# Cell_stretcher.net
KiCad netlist of a schematic drawn in EAGLE
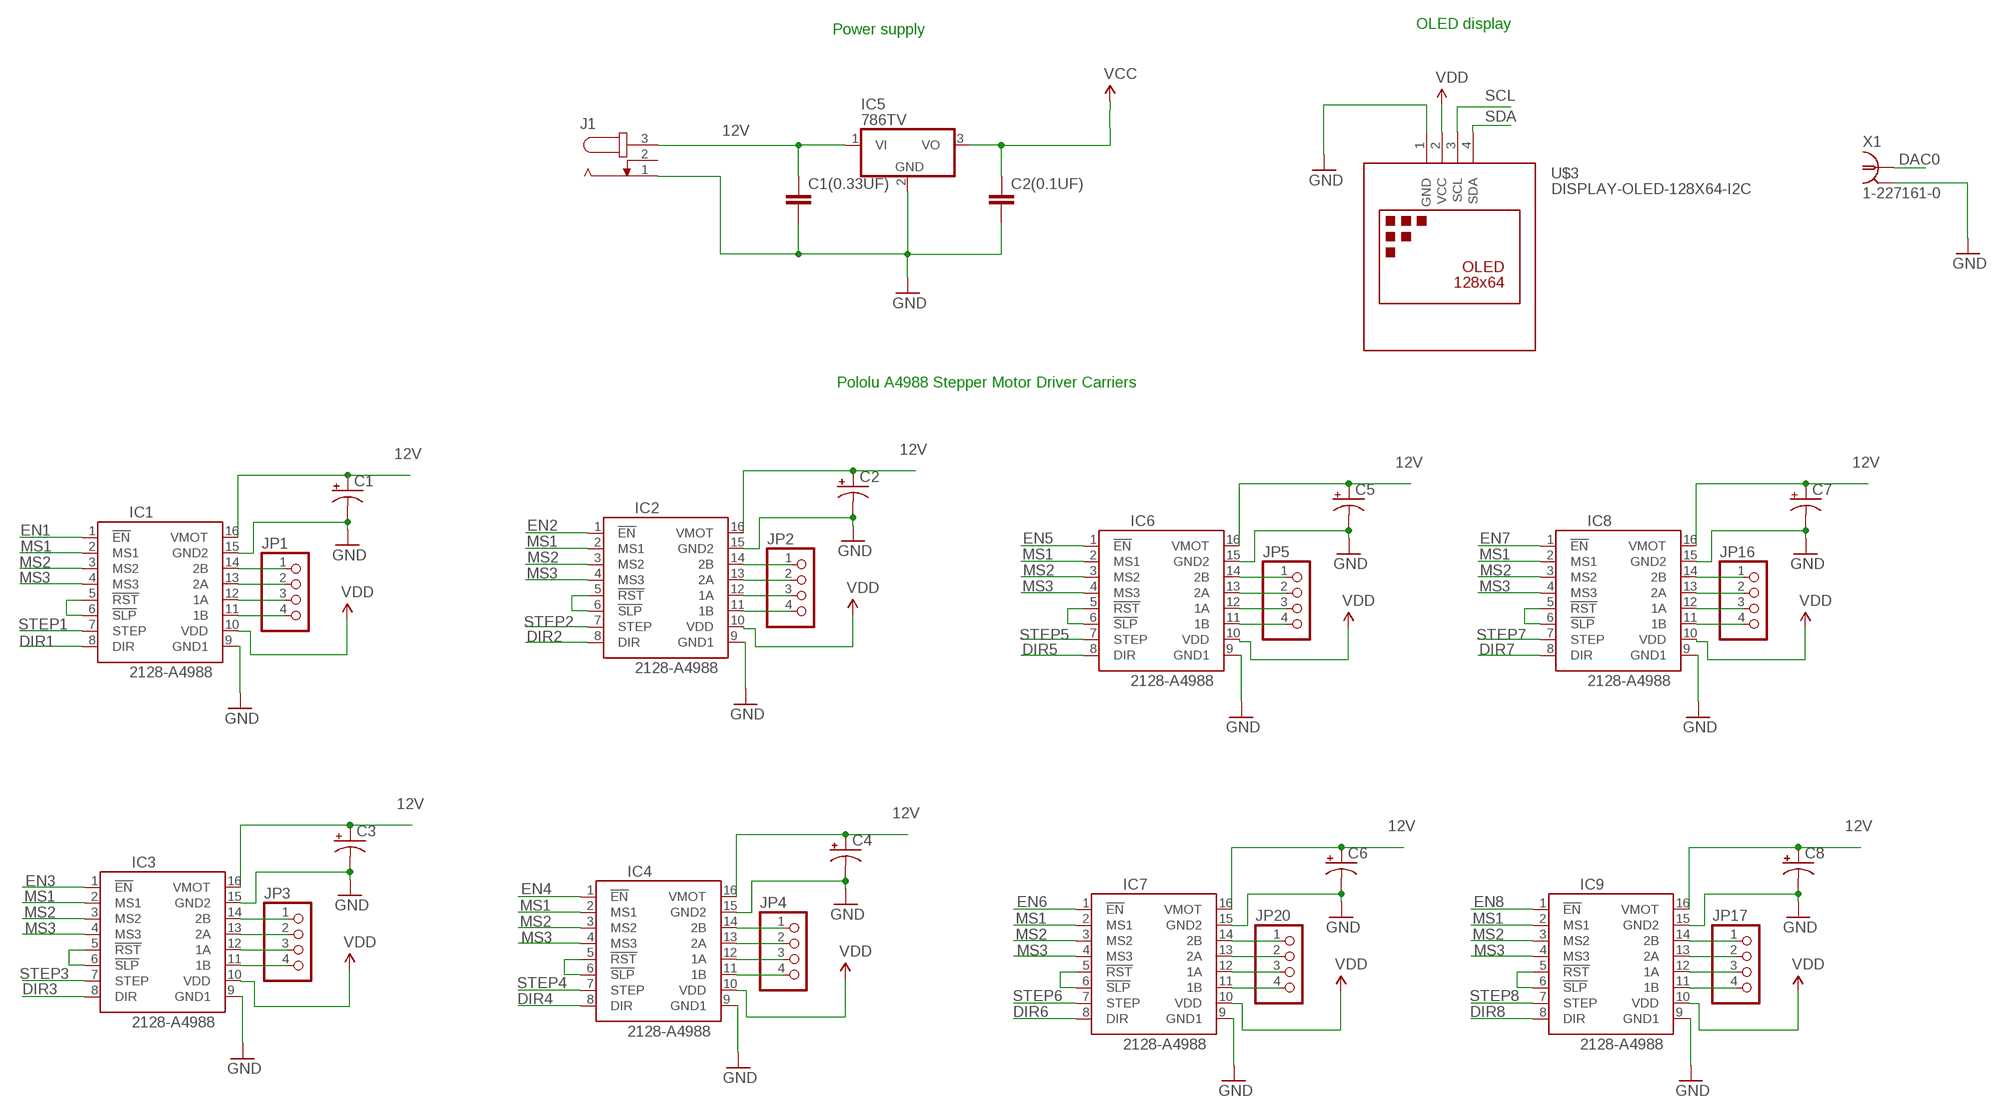
[diagram p0: schematic, sheet 1, part 1 of 2]
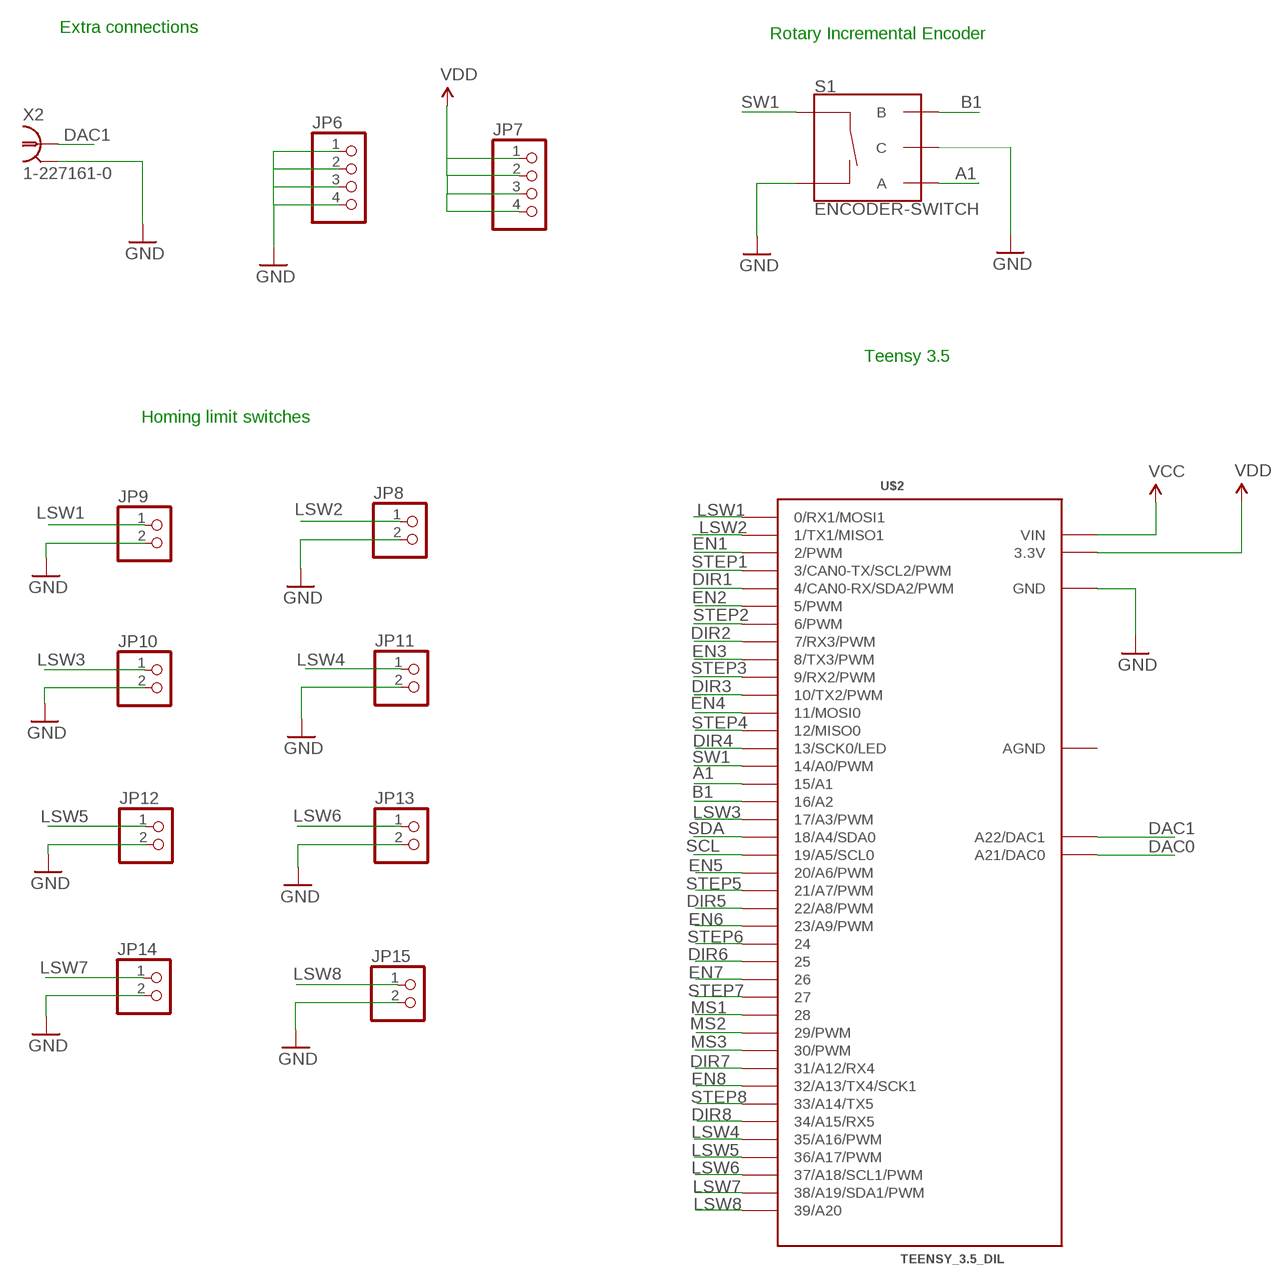
[diagram p1: schematic, sheet 1, part 2 of 2]

(export (version "E")
  (design (tool "Eeschema 10.0.6"))
  (components
    (comp (ref "C1")
      (value "CPOL-USE5-5")
      (footprint "eagle-import:E5-5")
      (libsource (lib "eagle-import") (part "CPOL-USE5-5"))
    )
    (comp (ref "C1(0.33UF)")
      (value "C2.5/4")
      (footprint "eagle-import:C2.5-4")
      (libsource (lib "eagle-import") (part "C2.5/4"))
    )
    (comp (ref "C2")
      (value "CPOL-USE5-5")
      (footprint "eagle-import:E5-5")
      (libsource (lib "eagle-import") (part "CPOL-USE5-5"))
    )
    (comp (ref "C2(0.1UF)")
      (value "C2.5/2")
      (footprint "eagle-import:C2.5-2")
      (libsource (lib "eagle-import") (part "C2.5/2"))
    )
    (comp (ref "C3")
      (value "CPOL-USE5-5")
      (footprint "eagle-import:E5-5")
      (libsource (lib "eagle-import") (part "CPOL-USE5-5"))
    )
    (comp (ref "C4")
      (value "CPOL-USE5-5")
      (footprint "eagle-import:E5-5")
      (libsource (lib "eagle-import") (part "CPOL-USE5-5"))
    )
    (comp (ref "C5")
      (value "CPOL-USE5-5")
      (footprint "eagle-import:E5-5")
      (libsource (lib "eagle-import") (part "CPOL-USE5-5"))
    )
    (comp (ref "C6")
      (value "CPOL-USE5-5")
      (footprint "eagle-import:E5-5")
      (libsource (lib "eagle-import") (part "CPOL-USE5-5"))
    )
    (comp (ref "C7")
      (value "CPOL-USE5-5")
      (footprint "eagle-import:E5-5")
      (libsource (lib "eagle-import") (part "CPOL-USE5-5"))
    )
    (comp (ref "C8")
      (value "CPOL-USE5-5")
      (footprint "eagle-import:E5-5")
      (libsource (lib "eagle-import") (part "CPOL-USE5-5"))
    )
    (comp (ref "IC1")
      (value "2128-A4988")
      (footprint "eagle-import:A4988")
      (libsource (lib "eagle-import") (part "2128-A4988"))
    )
    (comp (ref "IC2")
      (value "2128-A4988")
      (footprint "eagle-import:A4988")
      (libsource (lib "eagle-import") (part "2128-A4988"))
    )
    (comp (ref "IC3")
      (value "2128-A4988")
      (footprint "eagle-import:A4988")
      (libsource (lib "eagle-import") (part "2128-A4988"))
    )
    (comp (ref "IC4")
      (value "2128-A4988")
      (footprint "eagle-import:A4988")
      (libsource (lib "eagle-import") (part "2128-A4988"))
    )
    (comp (ref "IC5")
      (value "786TV")
      (footprint "eagle-import:TO220V")
      (libsource (lib "eagle-import") (part "78TV6"))
    )
    (comp (ref "IC6")
      (value "2128-A4988")
      (footprint "eagle-import:A4988")
      (libsource (lib "eagle-import") (part "2128-A4988"))
    )
    (comp (ref "IC7")
      (value "2128-A4988")
      (footprint "eagle-import:A4988")
      (libsource (lib "eagle-import") (part "2128-A4988"))
    )
    (comp (ref "IC8")
      (value "2128-A4988")
      (footprint "eagle-import:A4988")
      (libsource (lib "eagle-import") (part "2128-A4988"))
    )
    (comp (ref "IC9")
      (value "2128-A4988")
      (footprint "eagle-import:A4988")
      (libsource (lib "eagle-import") (part "2128-A4988"))
    )
    (comp (ref "J1")
      (value "JACK-PLUG0")
      (footprint "eagle-import:SPC4077")
      (libsource (lib "eagle-import") (part "JACK-PLUG0"))
    )
    (comp (ref "JP1")
      (value "PINHD-1X4")
      (footprint "eagle-import:1X04")
      (libsource (lib "eagle-import") (part "PINHD-1X4"))
    )
    (comp (ref "JP2")
      (value "PINHD-1X4")
      (footprint "eagle-import:1X04")
      (libsource (lib "eagle-import") (part "PINHD-1X4"))
    )
    (comp (ref "JP3")
      (value "PINHD-1X4")
      (footprint "eagle-import:1X04")
      (libsource (lib "eagle-import") (part "PINHD-1X4"))
    )
    (comp (ref "JP4")
      (value "PINHD-1X4")
      (footprint "eagle-import:1X04")
      (libsource (lib "eagle-import") (part "PINHD-1X4"))
    )
    (comp (ref "JP5")
      (value "PINHD-1X4")
      (footprint "eagle-import:1X04")
      (libsource (lib "eagle-import") (part "PINHD-1X4"))
    )
    (comp (ref "JP6")
      (value "PINHD-1X4")
      (footprint "eagle-import:1X04")
      (libsource (lib "eagle-import") (part "PINHD-1X4"))
    )
    (comp (ref "JP7")
      (value "PINHD-1X4")
      (footprint "eagle-import:1X04")
      (libsource (lib "eagle-import") (part "PINHD-1X4"))
    )
    (comp (ref "JP8")
      (value "PINHD-1X2")
      (footprint "eagle-import:1X02")
      (libsource (lib "eagle-import") (part "PINHD-1X2"))
    )
    (comp (ref "JP9")
      (value "PINHD-1X2")
      (footprint "eagle-import:1X02")
      (libsource (lib "eagle-import") (part "PINHD-1X2"))
    )
    (comp (ref "JP10")
      (value "PINHD-1X2")
      (footprint "eagle-import:1X02")
      (libsource (lib "eagle-import") (part "PINHD-1X2"))
    )
    (comp (ref "JP11")
      (value "PINHD-1X2")
      (footprint "eagle-import:1X02")
      (libsource (lib "eagle-import") (part "PINHD-1X2"))
    )
    (comp (ref "JP12")
      (value "PINHD-1X2")
      (footprint "eagle-import:1X02")
      (libsource (lib "eagle-import") (part "PINHD-1X2"))
    )
    (comp (ref "JP13")
      (value "PINHD-1X2")
      (footprint "eagle-import:1X02")
      (libsource (lib "eagle-import") (part "PINHD-1X2"))
    )
    (comp (ref "JP14")
      (value "PINHD-1X2")
      (footprint "eagle-import:1X02")
      (libsource (lib "eagle-import") (part "PINHD-1X2"))
    )
    (comp (ref "JP15")
      (value "PINHD-1X2")
      (footprint "eagle-import:1X02")
      (libsource (lib "eagle-import") (part "PINHD-1X2"))
    )
    (comp (ref "JP16")
      (value "PINHD-1X4")
      (footprint "eagle-import:1X04")
      (libsource (lib "eagle-import") (part "PINHD-1X4"))
    )
    (comp (ref "JP17")
      (value "PINHD-1X4")
      (footprint "eagle-import:1X04")
      (libsource (lib "eagle-import") (part "PINHD-1X4"))
    )
    (comp (ref "JP20")
      (value "PINHD-1X4")
      (footprint "eagle-import:1X04")
      (libsource (lib "eagle-import") (part "PINHD-1X4"))
    )
    (comp (ref "S1")
      (value "ENCODER-SWITCH")
      (footprint "eagle-import:ROTARY_ENC_PLAIN")
      (libsource (lib "eagle-import") (part "ENCODER-SWITCH"))
    )
    (comp (ref "U$2")
      (value "TEENSY_3.5_DIL")
      (footprint "eagle-import:TEENSY_3.5_DIL")
      (libsource (lib "eagle-import") (part "TEENSY_3.5_DIL"))
    )
    (comp (ref "U$3")
      (value "DISPLAY-OLED-128X64-I2C")
      (footprint "eagle-import:DISPLAY-OLED-128X64-I2C")
      (libsource (lib "eagle-import") (part "DISPLAY-OLED-128X64-I2C"))
    )
    (comp (ref "X1")
      (value "1-227161-0")
      (footprint "eagle-import:AMP_227161")
      (fields (field (name "MF") "TYCO ELECTRONICS") (field (name "MPN") "1-227161"))
      (libsource (lib "eagle-import") (part "?2271611--0"))
    )
    (comp (ref "X2")
      (value "1-227161-0")
      (footprint "eagle-import:AMP_227161")
      (fields (field (name "MF") "TYCO ELECTRONICS") (field (name "MPN") "1-227161"))
      (libsource (lib "eagle-import") (part "?2271611--0"))
    )
  )
  (nets
    (net (code "1") (name "/12V") (class "Default")
      (node (ref "C1") (pin "+") (pinfunction "+_+") (pintype "passive"))
      (node (ref "C1(0.33UF)") (pin "1") (pinfunction "1_1") (pintype "passive"))
      (node (ref "C2") (pin "+") (pinfunction "+_+") (pintype "passive"))
      (node (ref "C3") (pin "+") (pinfunction "+_+") (pintype "passive"))
      (node (ref "C4") (pin "+") (pinfunction "+_+") (pintype "passive"))
      (node (ref "C5") (pin "+") (pinfunction "+_+") (pintype "passive"))
      (node (ref "C6") (pin "+") (pinfunction "+_+") (pintype "passive"))
      (node (ref "C7") (pin "+") (pinfunction "+_+") (pintype "passive"))
      (node (ref "C8") (pin "+") (pinfunction "+_+") (pintype "passive"))
      (node (ref "IC1") (pin "16") (pinfunction "VMOT_16") (pintype "power_in"))
      (node (ref "IC2") (pin "16") (pinfunction "VMOT_16") (pintype "power_in"))
      (node (ref "IC3") (pin "16") (pinfunction "VMOT_16") (pintype "power_in"))
      (node (ref "IC4") (pin "16") (pinfunction "VMOT_16") (pintype "power_in"))
      (node (ref "IC5") (pin "1") (pinfunction "VI_1") (pintype "input"))
      (node (ref "IC6") (pin "16") (pinfunction "VMOT_16") (pintype "power_in"))
      (node (ref "IC7") (pin "16") (pinfunction "VMOT_16") (pintype "power_in"))
      (node (ref "IC8") (pin "16") (pinfunction "VMOT_16") (pintype "power_in"))
      (node (ref "IC9") (pin "16") (pinfunction "VMOT_16") (pintype "power_in"))
      (node (ref "J1") (pin "3") (pinfunction "3_3") (pintype "passive"))
    )
    (net (code "2") (name "/A1") (class "Default")
      (node (ref "S1") (pin "A") (pinfunction "A_A") (pintype "bidirectional"))
      (node (ref "U$2") (pin "15/A1") (pinfunction "15/A1_15/A1") (pintype "bidirectional"))
    )
    (net (code "3") (name "/AGND") (class "Default")
      (node (ref "U$2") (pin "AGND") (pinfunction "AGND_AGND") (pintype "power_in"))
    )
    (net (code "4") (name "/B1") (class "Default")
      (node (ref "S1") (pin "B") (pinfunction "B_B") (pintype "bidirectional"))
      (node (ref "U$2") (pin "16/A2") (pinfunction "16/A2_16/A2") (pintype "bidirectional"))
    )
    (net (code "5") (name "/DAC0") (class "Default")
      (node (ref "U$2") (pin "A21") (pinfunction "A21/DAC0_A21") (pintype "bidirectional"))
      (node (ref "X1") (pin "1") (pinfunction "1_1") (pintype "passive"))
    )
    (net (code "6") (name "/DAC1") (class "Default")
      (node (ref "U$2") (pin "A22") (pinfunction "A22/DAC1_A22") (pintype "bidirectional"))
      (node (ref "X2") (pin "1") (pinfunction "1_1") (pintype "passive"))
    )
    (net (code "7") (name "/DIR1") (class "Default")
      (node (ref "IC1") (pin "8") (pinfunction "DIR_8") (pintype "input"))
      (node (ref "U$2") (pin "4") (pinfunction "4/CAN0-RX/SDA2/PWM_4") (pintype "bidirectional"))
    )
    (net (code "8") (name "/DIR2") (class "Default")
      (node (ref "IC2") (pin "8") (pinfunction "DIR_8") (pintype "input"))
      (node (ref "U$2") (pin "7") (pinfunction "7/RX3/PWM_7") (pintype "bidirectional"))
    )
    (net (code "9") (name "/DIR3") (class "Default")
      (node (ref "IC3") (pin "8") (pinfunction "DIR_8") (pintype "input"))
      (node (ref "U$2") (pin "10") (pinfunction "10/TX2/PWM_10") (pintype "bidirectional"))
    )
    (net (code "10") (name "/DIR4") (class "Default")
      (node (ref "IC4") (pin "8") (pinfunction "DIR_8") (pintype "input"))
      (node (ref "U$2") (pin "13") (pinfunction "13/SCK0/LED_13") (pintype "bidirectional"))
    )
    (net (code "11") (name "/DIR5") (class "Default")
      (node (ref "IC6") (pin "8") (pinfunction "DIR_8") (pintype "input"))
      (node (ref "U$2") (pin "22/A8") (pinfunction "22/A8/PWM_22/A8") (pintype "bidirectional"))
    )
    (net (code "12") (name "/DIR6") (class "Default")
      (node (ref "IC7") (pin "8") (pinfunction "DIR_8") (pintype "input"))
      (node (ref "U$2") (pin "25") (pinfunction "25_25") (pintype "bidirectional"))
    )
    (net (code "13") (name "/DIR7") (class "Default")
      (node (ref "IC8") (pin "8") (pinfunction "DIR_8") (pintype "input"))
      (node (ref "U$2") (pin "31/A12") (pinfunction "31/A12/RX4_31/A12") (pintype "bidirectional"))
    )
    (net (code "14") (name "/DIR8") (class "Default")
      (node (ref "IC9") (pin "8") (pinfunction "DIR_8") (pintype "input"))
      (node (ref "U$2") (pin "34/A15") (pinfunction "34/A15/RX5_34/A15") (pintype "bidirectional"))
    )
    (net (code "15") (name "/EN1") (class "Default")
      (node (ref "IC1") (pin "1") (pinfunction "~{EN}_1") (pintype "passive"))
      (node (ref "U$2") (pin "2") (pinfunction "2/PWM_2") (pintype "bidirectional"))
    )
    (net (code "16") (name "/EN2") (class "Default")
      (node (ref "IC2") (pin "1") (pinfunction "~{EN}_1") (pintype "passive"))
      (node (ref "U$2") (pin "5") (pinfunction "5/PWM_5") (pintype "bidirectional"))
    )
    (net (code "17") (name "/EN3") (class "Default")
      (node (ref "IC3") (pin "1") (pinfunction "~{EN}_1") (pintype "passive"))
      (node (ref "U$2") (pin "8") (pinfunction "8/TX3/PWM_8") (pintype "bidirectional"))
    )
    (net (code "18") (name "/EN4") (class "Default")
      (node (ref "IC4") (pin "1") (pinfunction "~{EN}_1") (pintype "passive"))
      (node (ref "U$2") (pin "11") (pinfunction "11/MOSI0_11") (pintype "bidirectional"))
    )
    (net (code "19") (name "/EN5") (class "Default")
      (node (ref "IC6") (pin "1") (pinfunction "~{EN}_1") (pintype "passive"))
      (node (ref "U$2") (pin "20/A6") (pinfunction "20/A6/PWM_20/A6") (pintype "bidirectional"))
    )
    (net (code "20") (name "/EN6") (class "Default")
      (node (ref "IC7") (pin "1") (pinfunction "~{EN}_1") (pintype "passive"))
      (node (ref "U$2") (pin "23/A9") (pinfunction "23/A9/PWM_23/A9") (pintype "bidirectional"))
    )
    (net (code "21") (name "/EN7") (class "Default")
      (node (ref "IC8") (pin "1") (pinfunction "~{EN}_1") (pintype "passive"))
      (node (ref "U$2") (pin "26") (pinfunction "26_26") (pintype "bidirectional"))
    )
    (net (code "22") (name "/EN8") (class "Default")
      (node (ref "IC9") (pin "1") (pinfunction "~{EN}_1") (pintype "passive"))
      (node (ref "U$2") (pin "32/A13") (pinfunction "32/A13/TX4/SCK1_32/A13") (pintype "bidirectional"))
    )
    (net (code "23") (name "/LSW1") (class "Default")
      (node (ref "JP9") (pin "1") (pinfunction "1_1") (pintype "passive"))
      (node (ref "U$2") (pin "0") (pinfunction "0/RX1/MOSI1_0") (pintype "bidirectional"))
    )
    (net (code "24") (name "/LSW2") (class "Default")
      (node (ref "JP8") (pin "1") (pinfunction "1_1") (pintype "passive"))
      (node (ref "U$2") (pin "1") (pinfunction "1/TX1/MISO1_1") (pintype "bidirectional"))
    )
    (net (code "25") (name "/LSW3") (class "Default")
      (node (ref "JP10") (pin "1") (pinfunction "1_1") (pintype "passive"))
      (node (ref "U$2") (pin "17/A3") (pinfunction "17/A3/PWM_17/A3") (pintype "bidirectional"))
    )
    (net (code "26") (name "/LSW4") (class "Default")
      (node (ref "JP11") (pin "1") (pinfunction "1_1") (pintype "passive"))
      (node (ref "U$2") (pin "35/A16") (pinfunction "35/A16/PWM_35/A16") (pintype "bidirectional"))
    )
    (net (code "27") (name "/LSW5") (class "Default")
      (node (ref "JP12") (pin "1") (pinfunction "1_1") (pintype "passive"))
      (node (ref "U$2") (pin "36/A17") (pinfunction "36/A17/PWM_36/A17") (pintype "bidirectional"))
    )
    (net (code "28") (name "/LSW6") (class "Default")
      (node (ref "JP13") (pin "1") (pinfunction "1_1") (pintype "passive"))
      (node (ref "U$2") (pin "37/A18") (pinfunction "37/A18/SCL1/PWM_37/A18") (pintype "bidirectional"))
    )
    (net (code "29") (name "/LSW7") (class "Default")
      (node (ref "JP14") (pin "1") (pinfunction "1_1") (pintype "passive"))
      (node (ref "U$2") (pin "38/A19") (pinfunction "38/A19/SDA1/PWM_38/A19") (pintype "bidirectional"))
    )
    (net (code "30") (name "/LSW8") (class "Default")
      (node (ref "JP15") (pin "1") (pinfunction "1_1") (pintype "passive"))
      (node (ref "U$2") (pin "39/A20") (pinfunction "39/A20_39/A20") (pintype "bidirectional"))
    )
    (net (code "31") (name "/MS1") (class "Default")
      (node (ref "IC1") (pin "2") (pinfunction "MS1_2") (pintype "passive"))
      (node (ref "IC2") (pin "2") (pinfunction "MS1_2") (pintype "passive"))
      (node (ref "IC3") (pin "2") (pinfunction "MS1_2") (pintype "passive"))
      (node (ref "IC4") (pin "2") (pinfunction "MS1_2") (pintype "passive"))
      (node (ref "IC6") (pin "2") (pinfunction "MS1_2") (pintype "passive"))
      (node (ref "IC7") (pin "2") (pinfunction "MS1_2") (pintype "passive"))
      (node (ref "IC8") (pin "2") (pinfunction "MS1_2") (pintype "passive"))
      (node (ref "IC9") (pin "2") (pinfunction "MS1_2") (pintype "passive"))
      (node (ref "U$2") (pin "28") (pinfunction "28_28") (pintype "bidirectional"))
    )
    (net (code "32") (name "/MS2") (class "Default")
      (node (ref "IC1") (pin "3") (pinfunction "MS2_3") (pintype "passive"))
      (node (ref "IC2") (pin "3") (pinfunction "MS2_3") (pintype "passive"))
      (node (ref "IC3") (pin "3") (pinfunction "MS2_3") (pintype "passive"))
      (node (ref "IC4") (pin "3") (pinfunction "MS2_3") (pintype "passive"))
      (node (ref "IC6") (pin "3") (pinfunction "MS2_3") (pintype "passive"))
      (node (ref "IC7") (pin "3") (pinfunction "MS2_3") (pintype "passive"))
      (node (ref "IC8") (pin "3") (pinfunction "MS2_3") (pintype "passive"))
      (node (ref "IC9") (pin "3") (pinfunction "MS2_3") (pintype "passive"))
      (node (ref "U$2") (pin "29") (pinfunction "29/PWM_29") (pintype "bidirectional"))
    )
    (net (code "33") (name "/MS3") (class "Default")
      (node (ref "IC1") (pin "4") (pinfunction "MS3_4") (pintype "passive"))
      (node (ref "IC2") (pin "4") (pinfunction "MS3_4") (pintype "passive"))
      (node (ref "IC3") (pin "4") (pinfunction "MS3_4") (pintype "passive"))
      (node (ref "IC4") (pin "4") (pinfunction "MS3_4") (pintype "passive"))
      (node (ref "IC6") (pin "4") (pinfunction "MS3_4") (pintype "passive"))
      (node (ref "IC7") (pin "4") (pinfunction "MS3_4") (pintype "passive"))
      (node (ref "IC8") (pin "4") (pinfunction "MS3_4") (pintype "passive"))
      (node (ref "IC9") (pin "4") (pinfunction "MS3_4") (pintype "passive"))
      (node (ref "U$2") (pin "30") (pinfunction "30/PWM_30") (pintype "bidirectional"))
    )
    (net (code "34") (name "/SCL") (class "Default")
      (node (ref "U$2") (pin "19/A5") (pinfunction "19/A5/SCL0_19/A5") (pintype "bidirectional"))
      (node (ref "U$3") (pin "3") (pinfunction "SCL_3") (pintype "bidirectional"))
    )
    (net (code "35") (name "/SDA") (class "Default")
      (node (ref "U$2") (pin "18/A4") (pinfunction "18/A4/SDA0_18/A4") (pintype "bidirectional"))
      (node (ref "U$3") (pin "4") (pinfunction "SDA_4") (pintype "bidirectional"))
    )
    (net (code "36") (name "/STEP1") (class "Default")
      (node (ref "IC1") (pin "7") (pinfunction "STEP_7") (pintype "input"))
      (node (ref "U$2") (pin "3") (pinfunction "3/CAN0-TX/SCL2/PWM_3") (pintype "bidirectional"))
    )
    (net (code "37") (name "/STEP2") (class "Default")
      (node (ref "IC2") (pin "7") (pinfunction "STEP_7") (pintype "input"))
      (node (ref "U$2") (pin "6") (pinfunction "6/PWM_6") (pintype "bidirectional"))
    )
    (net (code "38") (name "/STEP3") (class "Default")
      (node (ref "IC3") (pin "7") (pinfunction "STEP_7") (pintype "input"))
      (node (ref "U$2") (pin "9") (pinfunction "9/RX2/PWM_9") (pintype "bidirectional"))
    )
    (net (code "39") (name "/STEP4") (class "Default")
      (node (ref "IC4") (pin "7") (pinfunction "STEP_7") (pintype "input"))
      (node (ref "U$2") (pin "12") (pinfunction "12/MISO0_12") (pintype "bidirectional"))
    )
    (net (code "40") (name "/STEP5") (class "Default")
      (node (ref "IC6") (pin "7") (pinfunction "STEP_7") (pintype "input"))
      (node (ref "U$2") (pin "21/A7") (pinfunction "21/A7/PWM_21/A7") (pintype "bidirectional"))
    )
    (net (code "41") (name "/STEP6") (class "Default")
      (node (ref "IC7") (pin "7") (pinfunction "STEP_7") (pintype "input"))
      (node (ref "U$2") (pin "24") (pinfunction "24_24") (pintype "bidirectional"))
    )
    (net (code "42") (name "/STEP7") (class "Default")
      (node (ref "IC8") (pin "7") (pinfunction "STEP_7") (pintype "input"))
      (node (ref "U$2") (pin "27") (pinfunction "27_27") (pintype "bidirectional"))
    )
    (net (code "43") (name "/STEP8") (class "Default")
      (node (ref "IC9") (pin "7") (pinfunction "STEP_7") (pintype "input"))
      (node (ref "U$2") (pin "33/A14") (pinfunction "33/A14/TX5_33/A14") (pintype "bidirectional"))
    )
    (net (code "44") (name "/SW1") (class "Default")
      (node (ref "S1") (pin "SW+") (pinfunction "SW+_SW+") (pintype "bidirectional"))
      (node (ref "U$2") (pin "14/A0") (pinfunction "14/A0/PWM_14/A0") (pintype "bidirectional"))
    )
    (net (code "45") (name "GND") (class "Default")
      (node (ref "C1") (pin "-") (pinfunction "-_-") (pintype "passive"))
      (node (ref "C1(0.33UF)") (pin "2") (pinfunction "2_2") (pintype "passive"))
      (node (ref "C2") (pin "-") (pinfunction "-_-") (pintype "passive"))
      (node (ref "C2(0.1UF)") (pin "2") (pinfunction "2_2") (pintype "passive"))
      (node (ref "C3") (pin "-") (pinfunction "-_-") (pintype "passive"))
      (node (ref "C4") (pin "-") (pinfunction "-_-") (pintype "passive"))
      (node (ref "C5") (pin "-") (pinfunction "-_-") (pintype "passive"))
      (node (ref "C6") (pin "-") (pinfunction "-_-") (pintype "passive"))
      (node (ref "C7") (pin "-") (pinfunction "-_-") (pintype "passive"))
      (node (ref "C8") (pin "-") (pinfunction "-_-") (pintype "passive"))
      (node (ref "IC1") (pin "15") (pinfunction "GND2_15") (pintype "power_in"))
      (node (ref "IC1") (pin "9") (pinfunction "GND1_9") (pintype "power_in"))
      (node (ref "IC2") (pin "15") (pinfunction "GND2_15") (pintype "power_in"))
      (node (ref "IC2") (pin "9") (pinfunction "GND1_9") (pintype "power_in"))
      (node (ref "IC3") (pin "15") (pinfunction "GND2_15") (pintype "power_in"))
      (node (ref "IC3") (pin "9") (pinfunction "GND1_9") (pintype "power_in"))
      (node (ref "IC4") (pin "15") (pinfunction "GND2_15") (pintype "power_in"))
      (node (ref "IC4") (pin "9") (pinfunction "GND1_9") (pintype "power_in"))
      (node (ref "IC5") (pin "2") (pinfunction "GND_2") (pintype "passive"))
      (node (ref "IC6") (pin "15") (pinfunction "GND2_15") (pintype "power_in"))
      (node (ref "IC6") (pin "9") (pinfunction "GND1_9") (pintype "power_in"))
      (node (ref "IC7") (pin "15") (pinfunction "GND2_15") (pintype "power_in"))
      (node (ref "IC7") (pin "9") (pinfunction "GND1_9") (pintype "power_in"))
      (node (ref "IC8") (pin "15") (pinfunction "GND2_15") (pintype "power_in"))
      (node (ref "IC8") (pin "9") (pinfunction "GND1_9") (pintype "power_in"))
      (node (ref "IC9") (pin "15") (pinfunction "GND2_15") (pintype "power_in"))
      (node (ref "IC9") (pin "9") (pinfunction "GND1_9") (pintype "power_in"))
      (node (ref "J1") (pin "1") (pinfunction "1_1") (pintype "passive"))
      (node (ref "JP10") (pin "2") (pinfunction "2_2") (pintype "passive"))
      (node (ref "JP11") (pin "2") (pinfunction "2_2") (pintype "passive"))
      (node (ref "JP12") (pin "2") (pinfunction "2_2") (pintype "passive"))
      (node (ref "JP13") (pin "2") (pinfunction "2_2") (pintype "passive"))
      (node (ref "JP14") (pin "2") (pinfunction "2_2") (pintype "passive"))
      (node (ref "JP15") (pin "2") (pinfunction "2_2") (pintype "passive"))
      (node (ref "JP6") (pin "1") (pinfunction "1_1") (pintype "passive"))
      (node (ref "JP6") (pin "2") (pinfunction "2_2") (pintype "passive"))
      (node (ref "JP6") (pin "3") (pinfunction "3_3") (pintype "passive"))
      (node (ref "JP6") (pin "4") (pinfunction "4_4") (pintype "passive"))
      (node (ref "JP8") (pin "2") (pinfunction "2_2") (pintype "passive"))
      (node (ref "JP9") (pin "2") (pinfunction "2_2") (pintype "passive"))
      (node (ref "S1") (pin "C") (pinfunction "C_C") (pintype "bidirectional"))
      (node (ref "S1") (pin "SW-") (pinfunction "SW-_SW-") (pintype "bidirectional"))
      (node (ref "U$2") (pin "GND") (pinfunction "GND_GND") (pintype "power_in"))
      (node (ref "U$2") (pin "GND1") (pinfunction "GND_GND1") (pintype "power_in"))
      (node (ref "U$3") (pin "1") (pinfunction "GND_1") (pintype "power_in"))
      (node (ref "X1") (pin "2") (pinfunction "2_2") (pintype "passive"))
      (node (ref "X2") (pin "2") (pinfunction "2_2") (pintype "passive"))
    )
    (net (code "46") (name "Net-(IC1-1A)") (class "Default")
      (node (ref "IC1") (pin "12") (pinfunction "1A_12") (pintype "output"))
      (node (ref "JP1") (pin "3") (pinfunction "3_3") (pintype "passive"))
    )
    (net (code "47") (name "Net-(IC1-1B)") (class "Default")
      (node (ref "IC1") (pin "11") (pinfunction "1B_11") (pintype "output"))
      (node (ref "JP1") (pin "4") (pinfunction "4_4") (pintype "passive"))
    )
    (net (code "48") (name "Net-(IC1-2A)") (class "Default")
      (node (ref "IC1") (pin "13") (pinfunction "2A_13") (pintype "output"))
      (node (ref "JP1") (pin "2") (pinfunction "2_2") (pintype "passive"))
    )
    (net (code "49") (name "Net-(IC1-2B)") (class "Default")
      (node (ref "IC1") (pin "14") (pinfunction "2B_14") (pintype "output"))
      (node (ref "JP1") (pin "1") (pinfunction "1_1") (pintype "passive"))
    )
    (net (code "50") (name "Net-(IC1-~{RST})") (class "Default")
      (node (ref "IC1") (pin "5") (pinfunction "~{RST}_5") (pintype "passive"))
      (node (ref "IC1") (pin "6") (pinfunction "~{SLP}_6") (pintype "passive"))
    )
    (net (code "51") (name "Net-(IC2-1A)") (class "Default")
      (node (ref "IC2") (pin "12") (pinfunction "1A_12") (pintype "output"))
      (node (ref "JP2") (pin "3") (pinfunction "3_3") (pintype "passive"))
    )
    (net (code "52") (name "Net-(IC2-1B)") (class "Default")
      (node (ref "IC2") (pin "11") (pinfunction "1B_11") (pintype "output"))
      (node (ref "JP2") (pin "4") (pinfunction "4_4") (pintype "passive"))
    )
    (net (code "53") (name "Net-(IC2-2A)") (class "Default")
      (node (ref "IC2") (pin "13") (pinfunction "2A_13") (pintype "output"))
      (node (ref "JP2") (pin "2") (pinfunction "2_2") (pintype "passive"))
    )
    (net (code "54") (name "Net-(IC2-2B)") (class "Default")
      (node (ref "IC2") (pin "14") (pinfunction "2B_14") (pintype "output"))
      (node (ref "JP2") (pin "1") (pinfunction "1_1") (pintype "passive"))
    )
    (net (code "55") (name "Net-(IC2-~{RST})") (class "Default")
      (node (ref "IC2") (pin "5") (pinfunction "~{RST}_5") (pintype "passive"))
      (node (ref "IC2") (pin "6") (pinfunction "~{SLP}_6") (pintype "passive"))
    )
    (net (code "56") (name "Net-(IC3-1A)") (class "Default")
      (node (ref "IC3") (pin "12") (pinfunction "1A_12") (pintype "output"))
      (node (ref "JP3") (pin "3") (pinfunction "3_3") (pintype "passive"))
    )
    (net (code "57") (name "Net-(IC3-1B)") (class "Default")
      (node (ref "IC3") (pin "11") (pinfunction "1B_11") (pintype "output"))
      (node (ref "JP3") (pin "4") (pinfunction "4_4") (pintype "passive"))
    )
    (net (code "58") (name "Net-(IC3-2A)") (class "Default")
      (node (ref "IC3") (pin "13") (pinfunction "2A_13") (pintype "output"))
      (node (ref "JP3") (pin "2") (pinfunction "2_2") (pintype "passive"))
    )
    (net (code "59") (name "Net-(IC3-2B)") (class "Default")
      (node (ref "IC3") (pin "14") (pinfunction "2B_14") (pintype "output"))
      (node (ref "JP3") (pin "1") (pinfunction "1_1") (pintype "passive"))
    )
    (net (code "60") (name "Net-(IC3-~{RST})") (class "Default")
      (node (ref "IC3") (pin "5") (pinfunction "~{RST}_5") (pintype "passive"))
      (node (ref "IC3") (pin "6") (pinfunction "~{SLP}_6") (pintype "passive"))
    )
    (net (code "61") (name "Net-(IC4-1A)") (class "Default")
      (node (ref "IC4") (pin "12") (pinfunction "1A_12") (pintype "output"))
      (node (ref "JP4") (pin "3") (pinfunction "3_3") (pintype "passive"))
    )
    (net (code "62") (name "Net-(IC4-1B)") (class "Default")
      (node (ref "IC4") (pin "11") (pinfunction "1B_11") (pintype "output"))
      (node (ref "JP4") (pin "4") (pinfunction "4_4") (pintype "passive"))
    )
    (net (code "63") (name "Net-(IC4-2A)") (class "Default")
      (node (ref "IC4") (pin "13") (pinfunction "2A_13") (pintype "output"))
      (node (ref "JP4") (pin "2") (pinfunction "2_2") (pintype "passive"))
    )
    (net (code "64") (name "Net-(IC4-2B)") (class "Default")
      (node (ref "IC4") (pin "14") (pinfunction "2B_14") (pintype "output"))
      (node (ref "JP4") (pin "1") (pinfunction "1_1") (pintype "passive"))
    )
    (net (code "65") (name "Net-(IC4-~{RST})") (class "Default")
      (node (ref "IC4") (pin "5") (pinfunction "~{RST}_5") (pintype "passive"))
      (node (ref "IC4") (pin "6") (pinfunction "~{SLP}_6") (pintype "passive"))
    )
    (net (code "66") (name "Net-(IC6-1A)") (class "Default")
      (node (ref "IC6") (pin "12") (pinfunction "1A_12") (pintype "output"))
      (node (ref "JP5") (pin "3") (pinfunction "3_3") (pintype "passive"))
    )
    (net (code "67") (name "Net-(IC6-1B)") (class "Default")
      (node (ref "IC6") (pin "11") (pinfunction "1B_11") (pintype "output"))
      (node (ref "JP5") (pin "4") (pinfunction "4_4") (pintype "passive"))
    )
    (net (code "68") (name "Net-(IC6-2A)") (class "Default")
      (node (ref "IC6") (pin "13") (pinfunction "2A_13") (pintype "output"))
      (node (ref "JP5") (pin "2") (pinfunction "2_2") (pintype "passive"))
    )
    (net (code "69") (name "Net-(IC6-2B)") (class "Default")
      (node (ref "IC6") (pin "14") (pinfunction "2B_14") (pintype "output"))
      (node (ref "JP5") (pin "1") (pinfunction "1_1") (pintype "passive"))
    )
    (net (code "70") (name "Net-(IC6-~{RST})") (class "Default")
      (node (ref "IC6") (pin "5") (pinfunction "~{RST}_5") (pintype "passive"))
      (node (ref "IC6") (pin "6") (pinfunction "~{SLP}_6") (pintype "passive"))
    )
    (net (code "71") (name "Net-(IC7-1A)") (class "Default")
      (node (ref "IC7") (pin "12") (pinfunction "1A_12") (pintype "output"))
      (node (ref "JP20") (pin "3") (pinfunction "3_3") (pintype "passive"))
    )
    (net (code "72") (name "Net-(IC7-1B)") (class "Default")
      (node (ref "IC7") (pin "11") (pinfunction "1B_11") (pintype "output"))
      (node (ref "JP20") (pin "4") (pinfunction "4_4") (pintype "passive"))
    )
    (net (code "73") (name "Net-(IC7-2A)") (class "Default")
      (node (ref "IC7") (pin "13") (pinfunction "2A_13") (pintype "output"))
      (node (ref "JP20") (pin "2") (pinfunction "2_2") (pintype "passive"))
    )
    (net (code "74") (name "Net-(IC7-2B)") (class "Default")
      (node (ref "IC7") (pin "14") (pinfunction "2B_14") (pintype "output"))
      (node (ref "JP20") (pin "1") (pinfunction "1_1") (pintype "passive"))
    )
    (net (code "75") (name "Net-(IC7-~{RST})") (class "Default")
      (node (ref "IC7") (pin "5") (pinfunction "~{RST}_5") (pintype "passive"))
      (node (ref "IC7") (pin "6") (pinfunction "~{SLP}_6") (pintype "passive"))
    )
    (net (code "76") (name "Net-(IC8-1A)") (class "Default")
      (node (ref "IC8") (pin "12") (pinfunction "1A_12") (pintype "output"))
      (node (ref "JP16") (pin "3") (pinfunction "3_3") (pintype "passive"))
    )
    (net (code "77") (name "Net-(IC8-1B)") (class "Default")
      (node (ref "IC8") (pin "11") (pinfunction "1B_11") (pintype "output"))
      (node (ref "JP16") (pin "4") (pinfunction "4_4") (pintype "passive"))
    )
    (net (code "78") (name "Net-(IC8-2A)") (class "Default")
      (node (ref "IC8") (pin "13") (pinfunction "2A_13") (pintype "output"))
      (node (ref "JP16") (pin "2") (pinfunction "2_2") (pintype "passive"))
    )
    (net (code "79") (name "Net-(IC8-2B)") (class "Default")
      (node (ref "IC8") (pin "14") (pinfunction "2B_14") (pintype "output"))
      (node (ref "JP16") (pin "1") (pinfunction "1_1") (pintype "passive"))
    )
    (net (code "80") (name "Net-(IC8-~{RST})") (class "Default")
      (node (ref "IC8") (pin "5") (pinfunction "~{RST}_5") (pintype "passive"))
      (node (ref "IC8") (pin "6") (pinfunction "~{SLP}_6") (pintype "passive"))
    )
    (net (code "81") (name "Net-(IC9-1A)") (class "Default")
      (node (ref "IC9") (pin "12") (pinfunction "1A_12") (pintype "output"))
      (node (ref "JP17") (pin "3") (pinfunction "3_3") (pintype "passive"))
    )
    (net (code "82") (name "Net-(IC9-1B)") (class "Default")
      (node (ref "IC9") (pin "11") (pinfunction "1B_11") (pintype "output"))
      (node (ref "JP17") (pin "4") (pinfunction "4_4") (pintype "passive"))
    )
    (net (code "83") (name "Net-(IC9-2A)") (class "Default")
      (node (ref "IC9") (pin "13") (pinfunction "2A_13") (pintype "output"))
      (node (ref "JP17") (pin "2") (pinfunction "2_2") (pintype "passive"))
    )
    (net (code "84") (name "Net-(IC9-2B)") (class "Default")
      (node (ref "IC9") (pin "14") (pinfunction "2B_14") (pintype "output"))
      (node (ref "JP17") (pin "1") (pinfunction "1_1") (pintype "passive"))
    )
    (net (code "85") (name "Net-(IC9-~{RST})") (class "Default")
      (node (ref "IC9") (pin "5") (pinfunction "~{RST}_5") (pintype "passive"))
      (node (ref "IC9") (pin "6") (pinfunction "~{SLP}_6") (pintype "passive"))
    )
    (net (code "86") (name "VCC") (class "Default")
      (node (ref "C2(0.1UF)") (pin "1") (pinfunction "1_1") (pintype "passive"))
      (node (ref "IC5") (pin "3") (pinfunction "VO_3") (pintype "passive"))
      (node (ref "U$2") (pin "VIN") (pinfunction "VIN_VIN") (pintype "power_in"))
    )
    (net (code "87") (name "VDD") (class "Default")
      (node (ref "IC1") (pin "10") (pinfunction "VDD_10") (pintype "power_in"))
      (node (ref "IC2") (pin "10") (pinfunction "VDD_10") (pintype "power_in"))
      (node (ref "IC3") (pin "10") (pinfunction "VDD_10") (pintype "power_in"))
      (node (ref "IC4") (pin "10") (pinfunction "VDD_10") (pintype "power_in"))
      (node (ref "IC6") (pin "10") (pinfunction "VDD_10") (pintype "power_in"))
      (node (ref "IC7") (pin "10") (pinfunction "VDD_10") (pintype "power_in"))
      (node (ref "IC8") (pin "10") (pinfunction "VDD_10") (pintype "power_in"))
      (node (ref "IC9") (pin "10") (pinfunction "VDD_10") (pintype "power_in"))
      (node (ref "JP7") (pin "1") (pinfunction "1_1") (pintype "passive"))
      (node (ref "JP7") (pin "2") (pinfunction "2_2") (pintype "passive"))
      (node (ref "JP7") (pin "3") (pinfunction "3_3") (pintype "passive"))
      (node (ref "JP7") (pin "4") (pinfunction "4_4") (pintype "passive"))
      (node (ref "U$2") (pin "3.3V") (pinfunction "3.3V_3.3V") (pintype "power_in"))
      (node (ref "U$2") (pin "3.3V3") (pinfunction "3.3V_3.3V3") (pintype "power_in"))
      (node (ref "U$3") (pin "2") (pinfunction "VCC_2") (pintype "power_in"))
    )
    (net (code "88") (name "unconnected-(J1-Pad2)") (class "Default")
      (node (ref "J1") (pin "2") (pinfunction "2_2") (pintype "passive"))
    )
  )
)
